# miniduino.net
KiCad netlist of a schematic drawn in EAGLE
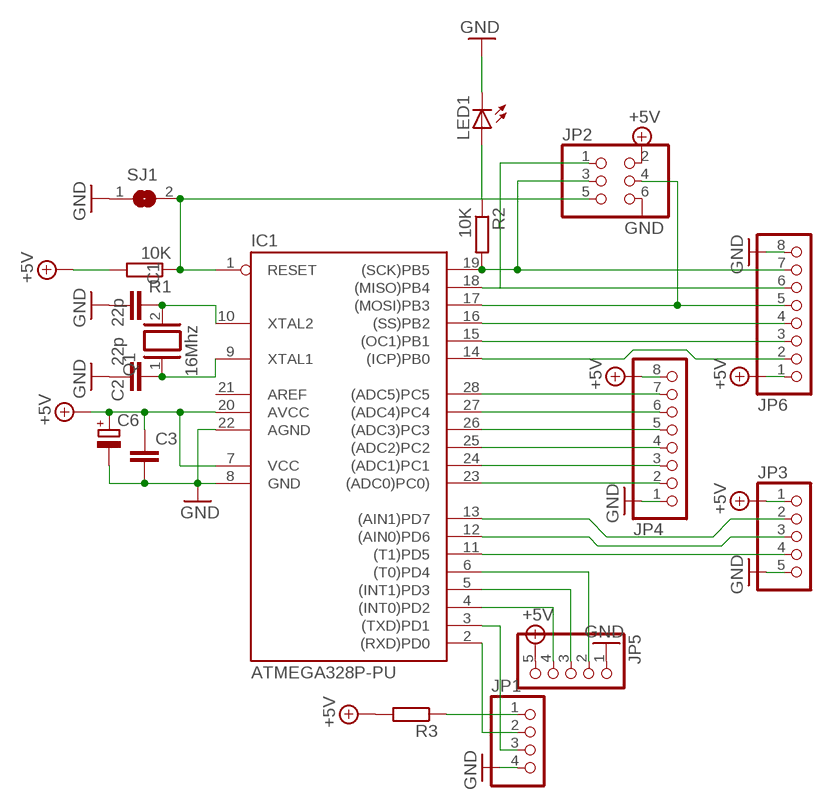
[diagram p0: schematic, sheet 1]

(export (version "E")
  (design (tool "Eeschema 10.0.6"))
  (components
    (comp (ref "C1")
      (value "22p")
      (footprint "eagle-import:C025-024X044")
      (libsource (lib "eagle-import") (part "resistor_C-EU025-024X044"))
    )
    (comp (ref "C2")
      (value "22p")
      (footprint "eagle-import:C025-024X044")
      (libsource (lib "eagle-import") (part "resistor_C-EU025-024X044"))
    )
    (comp (ref "C3")
      (value "C-EU050-025X075")
      (footprint "eagle-import:C050-025X075")
      (libsource (lib "eagle-import") (part "C-EU050-025X075"))
    )
    (comp (ref "C6")
      (value "CPOL-EUE2.5-5")
      (footprint "eagle-import:E2,5-5")
      (libsource (lib "eagle-import") (part "CPOL-EUE2.5-5"))
    )
    (comp (ref "IC1")
      (value "ATMEGA328P-PU")
      (footprint "eagle-import:DIL28-3")
      (libsource (lib "eagle-import") (part "ATMEGA328P-PU"))
    )
    (comp (ref "JP1")
      (value "PINHD-1X4")
      (footprint "eagle-import:1X04")
      (libsource (lib "eagle-import") (part "PINHD-1X4"))
    )
    (comp (ref "JP2")
      (value "PINHD-2X3")
      (footprint "eagle-import:2X03")
      (libsource (lib "eagle-import") (part "PINHD-2X3"))
    )
    (comp (ref "JP3")
      (value "PINHD-1X5")
      (footprint "eagle-import:1X05")
      (libsource (lib "eagle-import") (part "PINHD-1X5"))
    )
    (comp (ref "JP4")
      (value "PINHD-1X8")
      (footprint "eagle-import:1X08")
      (libsource (lib "eagle-import") (part "PINHD-1X8"))
    )
    (comp (ref "JP5")
      (value "PINHD-1X5")
      (footprint "eagle-import:1X05")
      (libsource (lib "eagle-import") (part "PINHD-1X5"))
    )
    (comp (ref "JP6")
      (value "PINHD-1X8")
      (footprint "eagle-import:1X08")
      (libsource (lib "eagle-import") (part "PINHD-1X8"))
    )
    (comp (ref "LED1")
      (value "LED3MM")
      (footprint "eagle-import:LED3MM")
      (libsource (lib "eagle-import") (part "LED3MM"))
    )
    (comp (ref "Q1")
      (value "16Mhz")
      (footprint "eagle-import:QS")
      (libsource (lib "eagle-import") (part "XTAL/S"))
    )
    (comp (ref "R1")
      (value "10K")
      (footprint "eagle-import:0204V")
      (libsource (lib "eagle-import") (part "resistor_R-EU_0204/2V"))
    )
    (comp (ref "R2")
      (value "10K")
      (footprint "eagle-import:0204V")
      (libsource (lib "eagle-import") (part "resistor_R-EU_0204/2V"))
    )
    (comp (ref "R3")
      (value "R-EU_0204/2V")
      (footprint "eagle-import:0204V")
      (libsource (lib "eagle-import") (part "R-EU_0204/2V"))
    )
    (comp (ref "SJ1") (value "SJ") (footprint "eagle-import:SJ") (libsource (lib "eagle-import") (part "SJ")))
  )
  (nets
    (net (code "1") (name "+5V") (class "Default")
      (node (ref "C3") (pin "1") (pinfunction "1_1") (pintype "passive"))
      (node (ref "C6") (pin "+") (pinfunction "+_+") (pintype "passive"))
      (node (ref "IC1") (pin "20") (pinfunction "AVCC_20") (pintype "power_in"))
      (node (ref "IC1") (pin "7") (pinfunction "VCC_7") (pintype "power_in"))
      (node (ref "JP2") (pin "2") (pinfunction "2_2") (pintype "passive"))
      (node (ref "JP3") (pin "1") (pinfunction "1_1") (pintype "passive"))
      (node (ref "JP4") (pin "8") (pinfunction "8_8") (pintype "passive"))
      (node (ref "JP5") (pin "5") (pinfunction "5_5") (pintype "passive"))
      (node (ref "JP6") (pin "1") (pinfunction "1_1") (pintype "passive"))
      (node (ref "R1") (pin "2") (pinfunction "2_2") (pintype "passive"))
      (node (ref "R3") (pin "2") (pinfunction "2_2") (pintype "passive"))
    )
    (net (code "2") (name "GND") (class "Default")
      (node (ref "C1") (pin "2") (pinfunction "2_2") (pintype "passive"))
      (node (ref "C2") (pin "1") (pinfunction "1_1") (pintype "passive"))
      (node (ref "C3") (pin "2") (pinfunction "2_2") (pintype "passive"))
      (node (ref "C6") (pin "-") (pinfunction "-_-") (pintype "passive"))
      (node (ref "IC1") (pin "22") (pinfunction "AGND_22") (pintype "power_in"))
      (node (ref "IC1") (pin "8") (pinfunction "GND_8") (pintype "power_in"))
      (node (ref "JP1") (pin "4") (pinfunction "4_4") (pintype "passive"))
      (node (ref "JP2") (pin "6") (pinfunction "6_6") (pintype "passive"))
      (node (ref "JP3") (pin "5") (pinfunction "5_5") (pintype "passive"))
      (node (ref "JP4") (pin "1") (pinfunction "1_1") (pintype "passive"))
      (node (ref "JP5") (pin "1") (pinfunction "1_1") (pintype "passive"))
      (node (ref "JP6") (pin "8") (pinfunction "8_8") (pintype "passive"))
      (node (ref "LED1") (pin "K") (pinfunction "C_K") (pintype "passive"))
      (node (ref "SJ1") (pin "1") (pinfunction "1_1") (pintype "passive"))
    )
    (net (code "3") (name "Net-(IC1-(ADC0)PC0))") (class "Default")
      (node (ref "IC1") (pin "23") (pinfunction "(ADC0)PC0)_23") (pintype "bidirectional"))
      (node (ref "JP4") (pin "2") (pinfunction "2_2") (pintype "passive"))
    )
    (net (code "4") (name "Net-(IC1-(ADC1)PC1)") (class "Default")
      (node (ref "IC1") (pin "24") (pinfunction "(ADC1)PC1_24") (pintype "bidirectional"))
      (node (ref "JP4") (pin "3") (pinfunction "3_3") (pintype "passive"))
    )
    (net (code "5") (name "Net-(IC1-(ADC2)PC2)") (class "Default")
      (node (ref "IC1") (pin "25") (pinfunction "(ADC2)PC2_25") (pintype "bidirectional"))
      (node (ref "JP4") (pin "4") (pinfunction "4_4") (pintype "passive"))
    )
    (net (code "6") (name "Net-(IC1-(ADC3)PC3)") (class "Default")
      (node (ref "IC1") (pin "26") (pinfunction "(ADC3)PC3_26") (pintype "bidirectional"))
      (node (ref "JP4") (pin "5") (pinfunction "5_5") (pintype "passive"))
    )
    (net (code "7") (name "Net-(IC1-(ADC4)PC4)") (class "Default")
      (node (ref "IC1") (pin "27") (pinfunction "(ADC4)PC4_27") (pintype "bidirectional"))
      (node (ref "JP4") (pin "6") (pinfunction "6_6") (pintype "passive"))
    )
    (net (code "8") (name "Net-(IC1-(ADC5)PC5)") (class "Default")
      (node (ref "IC1") (pin "28") (pinfunction "(ADC5)PC5_28") (pintype "bidirectional"))
      (node (ref "JP4") (pin "7") (pinfunction "7_7") (pintype "passive"))
    )
    (net (code "9") (name "Net-(IC1-(AIN0)PD6)") (class "Default")
      (node (ref "IC1") (pin "12") (pinfunction "(AIN0)PD6_12") (pintype "bidirectional"))
      (node (ref "JP3") (pin "3") (pinfunction "3_3") (pintype "passive"))
    )
    (net (code "10") (name "Net-(IC1-(AIN1)PD7)") (class "Default")
      (node (ref "IC1") (pin "13") (pinfunction "(AIN1)PD7_13") (pintype "bidirectional"))
      (node (ref "JP3") (pin "2") (pinfunction "2_2") (pintype "passive"))
    )
    (net (code "11") (name "Net-(IC1-(ICP)PB0)") (class "Default")
      (node (ref "IC1") (pin "14") (pinfunction "(ICP)PB0_14") (pintype "bidirectional"))
      (node (ref "JP6") (pin "2") (pinfunction "2_2") (pintype "passive"))
    )
    (net (code "12") (name "Net-(IC1-(INT0)PD2)") (class "Default")
      (node (ref "IC1") (pin "4") (pinfunction "(INT0)PD2_4") (pintype "bidirectional"))
      (node (ref "JP5") (pin "4") (pinfunction "4_4") (pintype "passive"))
    )
    (net (code "13") (name "Net-(IC1-(INT1)PD3)") (class "Default")
      (node (ref "IC1") (pin "5") (pinfunction "(INT1)PD3_5") (pintype "bidirectional"))
      (node (ref "JP5") (pin "3") (pinfunction "3_3") (pintype "passive"))
    )
    (net (code "14") (name "Net-(IC1-(MISO)PB4)") (class "Default")
      (node (ref "IC1") (pin "18") (pinfunction "(MISO)PB4_18") (pintype "bidirectional"))
      (node (ref "JP2") (pin "1") (pinfunction "1_1") (pintype "passive"))
      (node (ref "JP6") (pin "6") (pinfunction "6_6") (pintype "passive"))
    )
    (net (code "15") (name "Net-(IC1-(MOSI)PB3)") (class "Default")
      (node (ref "IC1") (pin "17") (pinfunction "(MOSI)PB3_17") (pintype "bidirectional"))
      (node (ref "JP2") (pin "4") (pinfunction "4_4") (pintype "passive"))
      (node (ref "JP6") (pin "5") (pinfunction "5_5") (pintype "passive"))
    )
    (net (code "16") (name "Net-(IC1-(OC1)PB1)") (class "Default")
      (node (ref "IC1") (pin "15") (pinfunction "(OC1)PB1_15") (pintype "bidirectional"))
      (node (ref "JP6") (pin "3") (pinfunction "3_3") (pintype "passive"))
    )
    (net (code "17") (name "Net-(IC1-(RXD)PD0)") (class "Default")
      (node (ref "IC1") (pin "2") (pinfunction "(RXD)PD0_2") (pintype "bidirectional"))
      (node (ref "JP1") (pin "2") (pinfunction "2_2") (pintype "passive"))
    )
    (net (code "18") (name "Net-(IC1-(SCK)PB5)") (class "Default")
      (node (ref "IC1") (pin "19") (pinfunction "(SCK)PB5_19") (pintype "bidirectional"))
      (node (ref "JP2") (pin "3") (pinfunction "3_3") (pintype "passive"))
      (node (ref "JP6") (pin "7") (pinfunction "7_7") (pintype "passive"))
      (node (ref "R2") (pin "2") (pinfunction "2_2") (pintype "passive"))
    )
    (net (code "19") (name "Net-(IC1-(SS)PB2)") (class "Default")
      (node (ref "IC1") (pin "16") (pinfunction "(SS)PB2_16") (pintype "bidirectional"))
      (node (ref "JP6") (pin "4") (pinfunction "4_4") (pintype "passive"))
    )
    (net (code "20") (name "Net-(IC1-(T0)PD4)") (class "Default")
      (node (ref "IC1") (pin "6") (pinfunction "(T0)PD4_6") (pintype "bidirectional"))
      (node (ref "JP5") (pin "2") (pinfunction "2_2") (pintype "passive"))
    )
    (net (code "21") (name "Net-(IC1-(T1)PD5)") (class "Default")
      (node (ref "IC1") (pin "11") (pinfunction "(T1)PD5_11") (pintype "bidirectional"))
      (node (ref "JP3") (pin "4") (pinfunction "4_4") (pintype "passive"))
    )
    (net (code "22") (name "Net-(IC1-(TXD)PD1)") (class "Default")
      (node (ref "IC1") (pin "3") (pinfunction "(TXD)PD1_3") (pintype "bidirectional"))
      (node (ref "JP1") (pin "3") (pinfunction "3_3") (pintype "passive"))
    )
    (net (code "23") (name "Net-(IC1-RESET)") (class "Default")
      (node (ref "IC1") (pin "1") (pinfunction "RESET_1") (pintype "input"))
      (node (ref "JP2") (pin "5") (pinfunction "5_5") (pintype "passive"))
      (node (ref "R1") (pin "1") (pinfunction "1_1") (pintype "passive"))
      (node (ref "SJ1") (pin "2") (pinfunction "2_2") (pintype "passive"))
    )
    (net (code "24") (name "Net-(IC1-XTAL1)") (class "Default")
      (node (ref "C2") (pin "2") (pinfunction "2_2") (pintype "passive"))
      (node (ref "IC1") (pin "9") (pinfunction "XTAL1_9") (pintype "bidirectional"))
      (node (ref "Q1") (pin "1") (pinfunction "1_1") (pintype "passive"))
    )
    (net (code "25") (name "Net-(IC1-XTAL2)") (class "Default")
      (node (ref "C1") (pin "1") (pinfunction "1_1") (pintype "passive"))
      (node (ref "IC1") (pin "10") (pinfunction "XTAL2_10") (pintype "bidirectional"))
      (node (ref "Q1") (pin "2") (pinfunction "2_2") (pintype "passive"))
    )
    (net (code "26") (name "Net-(JP1-Pad1)") (class "Default")
      (node (ref "JP1") (pin "1") (pinfunction "1_1") (pintype "passive"))
      (node (ref "R3") (pin "1") (pinfunction "1_1") (pintype "passive"))
    )
    (net (code "27") (name "Net-(LED1-PadA)") (class "Default")
      (node (ref "LED1") (pin "A") (pinfunction "A_A") (pintype "passive"))
      (node (ref "R2") (pin "1") (pinfunction "1_1") (pintype "passive"))
    )
    (net (code "28") (name "unconnected-(IC1-AREF-Pad21)") (class "Default")
      (node (ref "IC1") (pin "21") (pinfunction "AREF_21") (pintype "passive"))
    )
  )
)
